# Arduino.net
KiCad netlist of a schematic drawn in EAGLE
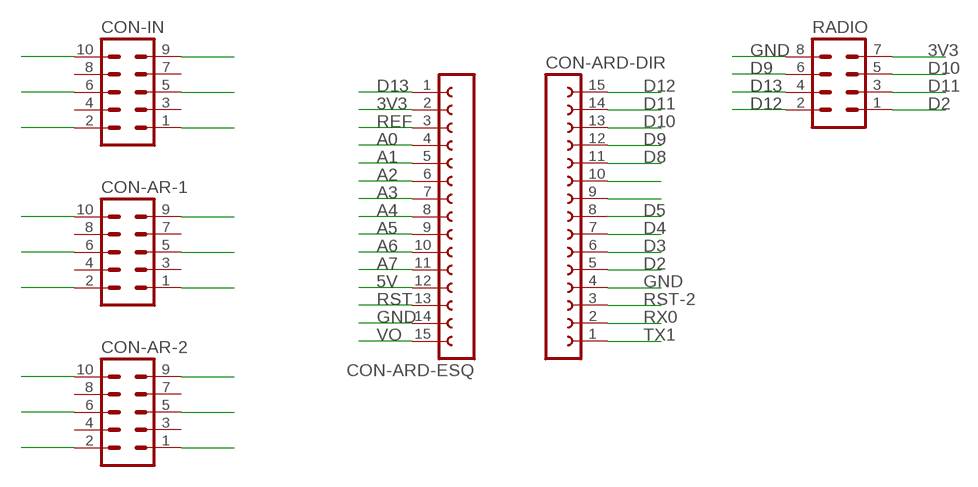
[diagram p0: schematic, sheet 1]

(export (version "E")
  (design (tool "Eeschema 10.0.6"))
  (components
    (comp (ref "CON-AR-1")
      (value "MA05-2")
      (footprint "eagle-import:MA05-2")
      (libsource (lib "eagle-import") (part "MA05-2"))
    )
    (comp (ref "CON-AR-2")
      (value "MA05-2")
      (footprint "eagle-import:MA05-2")
      (libsource (lib "eagle-import") (part "MA05-2"))
    )
    (comp (ref "CON-ARD-DIR")
      (value "FE15-1")
      (footprint "eagle-import:FE15")
      (libsource (lib "eagle-import") (part "FE15-1"))
    )
    (comp (ref "CON-ARD-ESQ")
      (value "FE15-1")
      (footprint "eagle-import:FE15")
      (libsource (lib "eagle-import") (part "FE15-1"))
    )
    (comp (ref "CON-IN")
      (value "MA05-2")
      (footprint "eagle-import:MA05-2")
      (libsource (lib "eagle-import") (part "MA05-2"))
    )
    (comp (ref "RADIO")
      (value "MA04-2")
      (footprint "eagle-import:MA04-2")
      (libsource (lib "eagle-import") (part "MA04-2"))
    )
  )
  (nets
    (net (code "1") (name "/3V3") (class "Default")
      (node (ref "CON-ARD-ESQ") (pin "2") (pinfunction "2_2") (pintype "passive"))
      (node (ref "RADIO") (pin "7") (pinfunction "7_7") (pintype "passive"))
    )
    (net (code "2") (name "/5V") (class "Default")
      (node (ref "CON-ARD-ESQ") (pin "12") (pinfunction "12_12") (pintype "passive"))
      (node (ref "CON-IN") (pin "5") (pinfunction "5_5") (pintype "passive"))
      (node (ref "CON-IN") (pin "6") (pinfunction "6_6") (pintype "passive"))
    )
    (net (code "3") (name "/A0") (class "Default")
      (node (ref "CON-ARD-ESQ") (pin "4") (pinfunction "4_4") (pintype "passive"))
    )
    (net (code "4") (name "/A1") (class "Default")
      (node (ref "CON-ARD-ESQ") (pin "5") (pinfunction "5_5") (pintype "passive"))
    )
    (net (code "5") (name "/A2") (class "Default")
      (node (ref "CON-ARD-ESQ") (pin "6") (pinfunction "6_6") (pintype "passive"))
    )
    (net (code "6") (name "/A3") (class "Default")
      (node (ref "CON-ARD-ESQ") (pin "7") (pinfunction "7_7") (pintype "passive"))
    )
    (net (code "7") (name "/A4") (class "Default")
      (node (ref "CON-ARD-ESQ") (pin "8") (pinfunction "8_8") (pintype "passive"))
    )
    (net (code "8") (name "/A5") (class "Default")
      (node (ref "CON-ARD-ESQ") (pin "9") (pinfunction "9_9") (pintype "passive"))
    )
    (net (code "9") (name "/A6") (class "Default")
      (node (ref "CON-ARD-ESQ") (pin "10") (pinfunction "10_10") (pintype "passive"))
    )
    (net (code "10") (name "/A7") (class "Default")
      (node (ref "CON-ARD-ESQ") (pin "11") (pinfunction "11_11") (pintype "passive"))
    )
    (net (code "11") (name "/D2") (class "Default")
      (node (ref "CON-ARD-DIR") (pin "5") (pinfunction "5_5") (pintype "passive"))
      (node (ref "RADIO") (pin "1") (pinfunction "1_1") (pintype "passive"))
    )
    (net (code "12") (name "/D3") (class "Default")
      (node (ref "CON-ARD-DIR") (pin "6") (pinfunction "6_6") (pintype "passive"))
    )
    (net (code "13") (name "/D4") (class "Default")
      (node (ref "CON-ARD-DIR") (pin "7") (pinfunction "7_7") (pintype "passive"))
    )
    (net (code "14") (name "/D5") (class "Default")
      (node (ref "CON-AR-2") (pin "1") (pinfunction "1_1") (pintype "passive"))
      (node (ref "CON-AR-2") (pin "2") (pinfunction "2_2") (pintype "passive"))
      (node (ref "CON-ARD-DIR") (pin "8") (pinfunction "8_8") (pintype "passive"))
    )
    (net (code "15") (name "/D6") (class "Default")
      (node (ref "CON-AR-1") (pin "10") (pinfunction "10_10") (pintype "passive"))
      (node (ref "CON-AR-1") (pin "9") (pinfunction "9_9") (pintype "passive"))
      (node (ref "CON-ARD-DIR") (pin "9") (pinfunction "9_9") (pintype "passive"))
    )
    (net (code "16") (name "/D7") (class "Default")
      (node (ref "CON-AR-1") (pin "5") (pinfunction "5_5") (pintype "passive"))
      (node (ref "CON-AR-1") (pin "6") (pinfunction "6_6") (pintype "passive"))
      (node (ref "CON-ARD-DIR") (pin "10") (pinfunction "10_10") (pintype "passive"))
    )
    (net (code "17") (name "/D8") (class "Default")
      (node (ref "CON-AR-1") (pin "1") (pinfunction "1_1") (pintype "passive"))
      (node (ref "CON-AR-1") (pin "2") (pinfunction "2_2") (pintype "passive"))
      (node (ref "CON-ARD-DIR") (pin "11") (pinfunction "11_11") (pintype "passive"))
    )
    (net (code "18") (name "/D9") (class "Default")
      (node (ref "CON-ARD-DIR") (pin "12") (pinfunction "12_12") (pintype "passive"))
      (node (ref "RADIO") (pin "6") (pinfunction "6_6") (pintype "passive"))
    )
    (net (code "19") (name "/D10") (class "Default")
      (node (ref "CON-ARD-DIR") (pin "13") (pinfunction "13_13") (pintype "passive"))
      (node (ref "RADIO") (pin "5") (pinfunction "5_5") (pintype "passive"))
    )
    (net (code "20") (name "/D11") (class "Default")
      (node (ref "CON-ARD-DIR") (pin "14") (pinfunction "14_14") (pintype "passive"))
      (node (ref "RADIO") (pin "3") (pinfunction "3_3") (pintype "passive"))
    )
    (net (code "21") (name "/D12") (class "Default")
      (node (ref "CON-ARD-DIR") (pin "15") (pinfunction "15_15") (pintype "passive"))
      (node (ref "RADIO") (pin "2") (pinfunction "2_2") (pintype "passive"))
    )
    (net (code "22") (name "/D13") (class "Default")
      (node (ref "CON-ARD-ESQ") (pin "1") (pinfunction "1_1") (pintype "passive"))
      (node (ref "RADIO") (pin "4") (pinfunction "4_4") (pintype "passive"))
    )
    (net (code "23") (name "/GND") (class "Default")
      (node (ref "CON-ARD-DIR") (pin "4") (pinfunction "4_4") (pintype "passive"))
      (node (ref "CON-ARD-ESQ") (pin "14") (pinfunction "14_14") (pintype "passive"))
      (node (ref "CON-IN") (pin "1") (pinfunction "1_1") (pintype "passive"))
      (node (ref "CON-IN") (pin "2") (pinfunction "2_2") (pintype "passive"))
      (node (ref "RADIO") (pin "8") (pinfunction "8_8") (pintype "passive"))
    )
    (net (code "24") (name "/REF") (class "Default")
      (node (ref "CON-ARD-ESQ") (pin "3") (pinfunction "3_3") (pintype "passive"))
    )
    (net (code "25") (name "/RST") (class "Default")
      (node (ref "CON-ARD-ESQ") (pin "13") (pinfunction "13_13") (pintype "passive"))
    )
    (net (code "26") (name "/RST-2") (class "Default")
      (node (ref "CON-ARD-DIR") (pin "3") (pinfunction "3_3") (pintype "passive"))
    )
    (net (code "27") (name "/RX0") (class "Default")
      (node (ref "CON-AR-2") (pin "5") (pinfunction "5_5") (pintype "passive"))
      (node (ref "CON-AR-2") (pin "6") (pinfunction "6_6") (pintype "passive"))
      (node (ref "CON-ARD-DIR") (pin "2") (pinfunction "2_2") (pintype "passive"))
    )
    (net (code "28") (name "/TX1") (class "Default")
      (node (ref "CON-AR-2") (pin "10") (pinfunction "10_10") (pintype "passive"))
      (node (ref "CON-AR-2") (pin "9") (pinfunction "9_9") (pintype "passive"))
      (node (ref "CON-ARD-DIR") (pin "1") (pinfunction "1_1") (pintype "passive"))
    )
    (net (code "29") (name "/VO") (class "Default")
      (node (ref "CON-ARD-ESQ") (pin "15") (pinfunction "15_15") (pintype "passive"))
      (node (ref "CON-IN") (pin "10") (pinfunction "10_10") (pintype "passive"))
      (node (ref "CON-IN") (pin "9") (pinfunction "9_9") (pintype "passive"))
    )
    (net (code "30") (name "unconnected-(CON-AR-1-Pad3)") (class "Default")
      (node (ref "CON-AR-1") (pin "3") (pinfunction "3_3") (pintype "passive"))
    )
    (net (code "31") (name "unconnected-(CON-AR-1-Pad4)") (class "Default")
      (node (ref "CON-AR-1") (pin "4") (pinfunction "4_4") (pintype "passive"))
    )
    (net (code "32") (name "unconnected-(CON-AR-1-Pad7)") (class "Default")
      (node (ref "CON-AR-1") (pin "7") (pinfunction "7_7") (pintype "passive"))
    )
    (net (code "33") (name "unconnected-(CON-AR-1-Pad8)") (class "Default")
      (node (ref "CON-AR-1") (pin "8") (pinfunction "8_8") (pintype "passive"))
    )
    (net (code "34") (name "unconnected-(CON-AR-2-Pad3)") (class "Default")
      (node (ref "CON-AR-2") (pin "3") (pinfunction "3_3") (pintype "passive"))
    )
    (net (code "35") (name "unconnected-(CON-AR-2-Pad4)") (class "Default")
      (node (ref "CON-AR-2") (pin "4") (pinfunction "4_4") (pintype "passive"))
    )
    (net (code "36") (name "unconnected-(CON-AR-2-Pad7)") (class "Default")
      (node (ref "CON-AR-2") (pin "7") (pinfunction "7_7") (pintype "passive"))
    )
    (net (code "37") (name "unconnected-(CON-AR-2-Pad8)") (class "Default")
      (node (ref "CON-AR-2") (pin "8") (pinfunction "8_8") (pintype "passive"))
    )
    (net (code "38") (name "unconnected-(CON-IN-Pad3)") (class "Default")
      (node (ref "CON-IN") (pin "3") (pinfunction "3_3") (pintype "passive"))
    )
    (net (code "39") (name "unconnected-(CON-IN-Pad4)") (class "Default")
      (node (ref "CON-IN") (pin "4") (pinfunction "4_4") (pintype "passive"))
    )
    (net (code "40") (name "unconnected-(CON-IN-Pad7)") (class "Default")
      (node (ref "CON-IN") (pin "7") (pinfunction "7_7") (pintype "passive"))
    )
    (net (code "41") (name "unconnected-(CON-IN-Pad8)") (class "Default")
      (node (ref "CON-IN") (pin "8") (pinfunction "8_8") (pintype "passive"))
    )
  )
)
